# SwitchMatrixSchem.net
KiCad netlist of a schematic drawn in Altium Designer
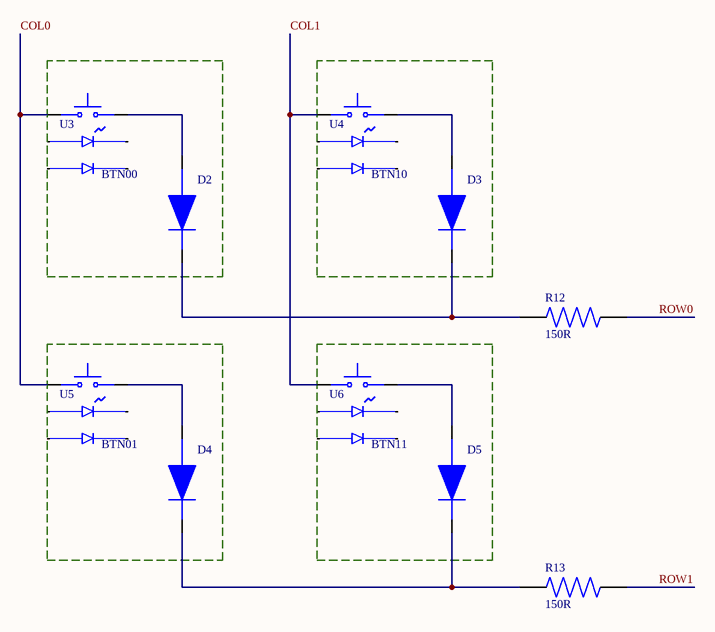
[diagram p0: SwitchMatrixSchem.SchDoc]

(export (version "E")
  (design (tool "Eeschema 10.0.6"))
  (components
    (comp (ref "D2")
      (value "RectifierDiode")
      (footprint "DO-219AB_VIS-M")
      (description "VISHAY - ES07D-GS08 - Fast / Ultrafast Diode, 200 V, 1.2 A, Single, 980 mV, 25 ns, 30 A")
      (fields (field (name "MANUFACTURER") "Vishay") (field (name "MANUFACTURER PART NUMBER") "ES07D-GS08"))
      (libsource (lib "MediaControllerSchLib") (part "ES07D-GS08"))
    )
    (comp (ref "D3")
      (value "RectifierDiode")
      (footprint "DO-219AB_VIS-M")
      (description "VISHAY - ES07D-GS08 - Fast / Ultrafast Diode, 200 V, 1.2 A, Single, 980 mV, 25 ns, 30 A")
      (fields (field (name "MANUFACTURER") "Vishay") (field (name "MANUFACTURER PART NUMBER") "ES07D-GS08"))
      (libsource (lib "MediaControllerSchLib") (part "ES07D-GS08"))
    )
    (comp (ref "D4")
      (value "RectifierDiode")
      (footprint "DO-219AB_VIS-M")
      (description "VISHAY - ES07D-GS08 - Fast / Ultrafast Diode, 200 V, 1.2 A, Single, 980 mV, 25 ns, 30 A")
      (fields (field (name "MANUFACTURER") "Vishay") (field (name "MANUFACTURER PART NUMBER") "ES07D-GS08"))
      (libsource (lib "MediaControllerSchLib") (part "ES07D-GS08"))
    )
    (comp (ref "D5")
      (value "RectifierDiode")
      (footprint "DO-219AB_VIS-M")
      (description "VISHAY - ES07D-GS08 - Fast / Ultrafast Diode, 200 V, 1.2 A, Single, 980 mV, 25 ns, 30 A")
      (fields (field (name "MANUFACTURER") "Vishay") (field (name "MANUFACTURER PART NUMBER") "ES07D-GS08"))
      (libsource (lib "MediaControllerSchLib") (part "ES07D-GS08"))
    )
    (comp (ref "R12")
      (value "150R")
      (footprint "RES0608_150OHM")
      (description "Res Thick Film 0603 150 Ohm 1% 0.33W(1/3W) ±100ppm/°C Pad SMD Automotive T/R")
      (fields
        (field (name "MANUFACTURER") "Vishay")
        (field (name "MANUFACTURER PART NUMBER") "CRCW0603150RFKEAHP")
      )
      (libsource (lib "MediaControllerSchLib") (part "CRCW0603150RFKEAHP"))
    )
    (comp (ref "R13")
      (value "150R")
      (footprint "RES0608_150OHM")
      (description "Res Thick Film 0603 150 Ohm 1% 0.33W(1/3W) ±100ppm/°C Pad SMD Automotive T/R")
      (fields
        (field (name "MANUFACTURER") "Vishay")
        (field (name "MANUFACTURER PART NUMBER") "CRCW0603150RFKEAHP")
      )
      (libsource (lib "MediaControllerSchLib") (part "CRCW0603150RFKEAHP"))
    )
    (comp (ref "U3")
      (value "Switch")
      (footprint "CHERRYMX_5PIN")
      (description "ZF CHERRY   MX1A-E1NN   SWITCH, TACTILE, SPST-NO, 10mA, THOUGH HOLE")
      (fields (field (name "MANUFACTURER") "Cherry") (field (name "MANUFACTURER PART NUMBER") "MX1A-E1NN"))
      (libsource (lib "MediaControllerSchLib") (part "CherryMXKeyswitch"))
    )
    (comp (ref "U4")
      (value "Switch")
      (footprint "CHERRYMX_5PIN")
      (description "ZF CHERRY   MX1A-E1NN   SWITCH, TACTILE, SPST-NO, 10mA, THOUGH HOLE")
      (fields (field (name "MANUFACTURER") "Cherry") (field (name "MANUFACTURER PART NUMBER") "MX1A-E1NN"))
      (libsource (lib "MediaControllerSchLib") (part "CherryMXKeyswitch"))
    )
    (comp (ref "U5")
      (value "Switch")
      (footprint "CHERRYMX_5PIN")
      (description "ZF CHERRY   MX1A-E1NN   SWITCH, TACTILE, SPST-NO, 10mA, THOUGH HOLE")
      (fields (field (name "MANUFACTURER") "Cherry") (field (name "MANUFACTURER PART NUMBER") "MX1A-E1NN"))
      (libsource (lib "MediaControllerSchLib") (part "CherryMXKeyswitch"))
    )
    (comp (ref "U6")
      (value "Switch")
      (footprint "CHERRYMX_5PIN")
      (description "ZF CHERRY   MX1A-E1NN   SWITCH, TACTILE, SPST-NO, 10mA, THOUGH HOLE")
      (fields (field (name "MANUFACTURER") "Cherry") (field (name "MANUFACTURER PART NUMBER") "MX1A-E1NN"))
      (libsource (lib "MediaControllerSchLib") (part "CherryMXKeyswitch"))
    )
  )
  (nets
    (net (code "1") (name "/COL0") (class "Default")
      (node (ref "U3") (pin "1") (pinfunction "1_1") (pintype "passive"))
      (node (ref "U5") (pin "1") (pinfunction "1_1") (pintype "passive"))
    )
    (net (code "2") (name "/COL1") (class "Default")
      (node (ref "U4") (pin "1") (pinfunction "1_1") (pintype "passive"))
      (node (ref "U6") (pin "1") (pinfunction "1_1") (pintype "passive"))
    )
    (net (code "3") (name "/ROW0") (class "Default")
      (node (ref "R12") (pin "2") (pinfunction "2_2") (pintype "passive"))
    )
    (net (code "4") (name "/ROW1") (class "Default")
      (node (ref "R13") (pin "2") (pinfunction "2_2") (pintype "passive"))
    )
    (net (code "5") (name "Net-(D2-Pad1)") (class "Default")
      (node (ref "D2") (pin "1") (pinfunction "1_1") (pintype "passive"))
      (node (ref "U3") (pin "2") (pinfunction "2_2") (pintype "passive"))
    )
    (net (code "6") (name "Net-(D2-Pad2)") (class "Default")
      (node (ref "D2") (pin "2") (pinfunction "2_2") (pintype "passive"))
      (node (ref "D3") (pin "2") (pinfunction "2_2") (pintype "passive"))
      (node (ref "R12") (pin "1") (pinfunction "1_1") (pintype "passive"))
    )
    (net (code "7") (name "Net-(D3-Pad1)") (class "Default")
      (node (ref "D3") (pin "1") (pinfunction "1_1") (pintype "passive"))
      (node (ref "U4") (pin "2") (pinfunction "2_2") (pintype "passive"))
    )
    (net (code "8") (name "Net-(D4-Pad1)") (class "Default")
      (node (ref "D4") (pin "1") (pinfunction "1_1") (pintype "passive"))
      (node (ref "U5") (pin "2") (pinfunction "2_2") (pintype "passive"))
    )
    (net (code "9") (name "Net-(D4-Pad2)") (class "Default")
      (node (ref "D4") (pin "2") (pinfunction "2_2") (pintype "passive"))
      (node (ref "D5") (pin "2") (pinfunction "2_2") (pintype "passive"))
      (node (ref "R13") (pin "1") (pinfunction "1_1") (pintype "passive"))
    )
    (net (code "10") (name "Net-(D5-Pad1)") (class "Default")
      (node (ref "D5") (pin "1") (pinfunction "1_1") (pintype "passive"))
      (node (ref "U6") (pin "2") (pinfunction "2_2") (pintype "passive"))
    )
    (net (code "11") (name "unconnected-(U3-Pad3)") (class "Default")
      (node (ref "U3") (pin "3") (pinfunction "3_3") (pintype "passive"))
    )
    (net (code "12") (name "unconnected-(U3-Pad4)") (class "Default")
      (node (ref "U3") (pin "4") (pinfunction "4_4") (pintype "passive"))
    )
    (net (code "13") (name "unconnected-(U3-Pad5)") (class "Default")
      (node (ref "U3") (pin "5") (pinfunction "5_5") (pintype "passive"))
    )
    (net (code "14") (name "unconnected-(U3-Pad6)") (class "Default")
      (node (ref "U3") (pin "6") (pinfunction "6_6") (pintype "passive"))
    )
    (net (code "15") (name "unconnected-(U4-Pad3)") (class "Default")
      (node (ref "U4") (pin "3") (pinfunction "3_3") (pintype "passive"))
    )
    (net (code "16") (name "unconnected-(U4-Pad4)") (class "Default")
      (node (ref "U4") (pin "4") (pinfunction "4_4") (pintype "passive"))
    )
    (net (code "17") (name "unconnected-(U4-Pad5)") (class "Default")
      (node (ref "U4") (pin "5") (pinfunction "5_5") (pintype "passive"))
    )
    (net (code "18") (name "unconnected-(U4-Pad6)") (class "Default")
      (node (ref "U4") (pin "6") (pinfunction "6_6") (pintype "passive"))
    )
    (net (code "19") (name "unconnected-(U5-Pad3)") (class "Default")
      (node (ref "U5") (pin "3") (pinfunction "3_3") (pintype "passive"))
    )
    (net (code "20") (name "unconnected-(U5-Pad4)") (class "Default")
      (node (ref "U5") (pin "4") (pinfunction "4_4") (pintype "passive"))
    )
    (net (code "21") (name "unconnected-(U5-Pad5)") (class "Default")
      (node (ref "U5") (pin "5") (pinfunction "5_5") (pintype "passive"))
    )
    (net (code "22") (name "unconnected-(U5-Pad6)") (class "Default")
      (node (ref "U5") (pin "6") (pinfunction "6_6") (pintype "passive"))
    )
    (net (code "23") (name "unconnected-(U6-Pad3)") (class "Default")
      (node (ref "U6") (pin "3") (pinfunction "3_3") (pintype "passive"))
    )
    (net (code "24") (name "unconnected-(U6-Pad4)") (class "Default")
      (node (ref "U6") (pin "4") (pinfunction "4_4") (pintype "passive"))
    )
    (net (code "25") (name "unconnected-(U6-Pad5)") (class "Default")
      (node (ref "U6") (pin "5") (pinfunction "5_5") (pintype "passive"))
    )
    (net (code "26") (name "unconnected-(U6-Pad6)") (class "Default")
      (node (ref "U6") (pin "6") (pinfunction "6_6") (pintype "passive"))
    )
  )
)
